# igniter.net
KiCad netlist of a schematic drawn in EAGLE
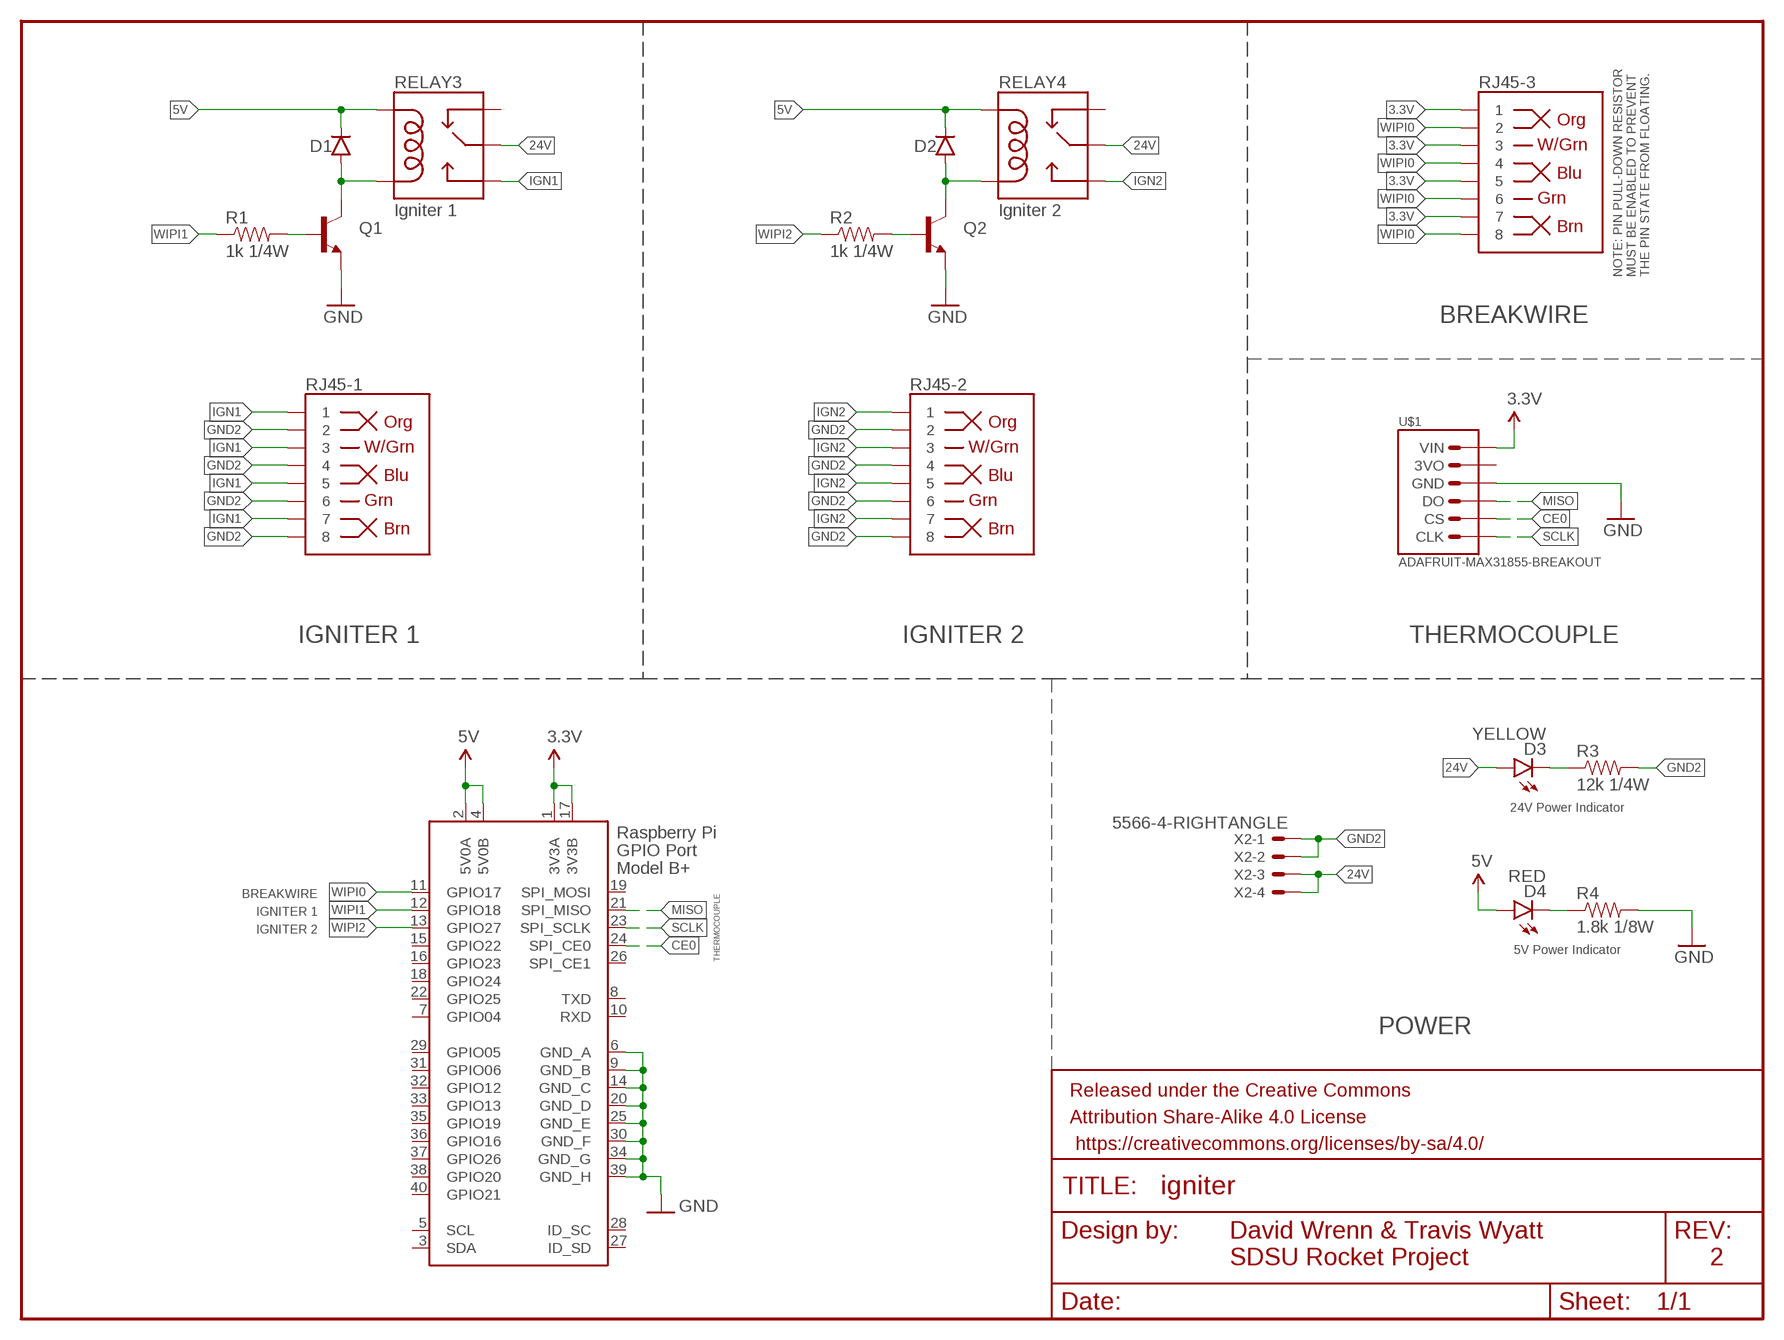
[diagram p0: schematic, sheet 1]

(export (version "E")
  (design (tool "Eeschema 10.0.6"))
  (components
    (comp (ref "D1")
      (value "DIODEPTH")
      (footprint "eagle-import:DIODE-1N4001")
      (libsource (lib "eagle-import") (part "DIODEPTH"))
    )
    (comp (ref "D2")
      (value "DIODEPTH")
      (footprint "eagle-import:DIODE-1N4001")
      (libsource (lib "eagle-import") (part "DIODEPTH"))
    )
    (comp (ref "D3")
      (value "YELLOW")
      (footprint "eagle-import:LED-0603")
      (libsource (lib "eagle-import") (part "LED0603"))
    )
    (comp (ref "D4")
      (value "RED")
      (footprint "eagle-import:LED-0603")
      (libsource (lib "eagle-import") (part "LED0603"))
    )
    (comp (ref "FRAME1")
      (value "FRAME-LETTER")
      (footprint "eagle-import:CREATIVE_COMMONS")
      (fields (field (name "DESIGNER") "NAME"))
      (libsource (lib "eagle-import") (part "FRAME-LETTER"))
    )
    (comp (ref "Q1")
      (value "TRANSISTOR_NPNP2N2222A")
      (footprint "eagle-import:TO-92")
      (libsource (lib "eagle-import") (part "TRANSISTOR_NPNP2N2222A"))
    )
    (comp (ref "Q2")
      (value "TRANSISTOR_NPNP2N2222A")
      (footprint "eagle-import:TO-92")
      (libsource (lib "eagle-import") (part "TRANSISTOR_NPNP2N2222A"))
    )
    (comp (ref "R1")
      (value "1k 1/4W")
      (footprint "eagle-import:AXIAL-0.3")
      (libsource (lib "eagle-import") (part "RESISTORAXIAL-0.3"))
    )
    (comp (ref "R2")
      (value "1k 1/4W")
      (footprint "eagle-import:AXIAL-0.3")
      (libsource (lib "eagle-import") (part "RESISTORAXIAL-0.3"))
    )
    (comp (ref "R3")
      (value "12k 1/4W")
      (footprint "eagle-import:0603-RES")
      (libsource (lib "eagle-import") (part "RESISTOR0603-RES"))
    )
    (comp (ref "R4")
      (value "1.8k 1/8W")
      (footprint "eagle-import:0603-RES")
      (libsource (lib "eagle-import") (part "RESISTOR0603-RES"))
    )
    (comp (ref "RELAY3")
      (value "Igniter 1")
      (footprint "eagle-import:RELAY-G5Q")
      (libsource (lib "eagle-import") (part "RELAYPTH"))
    )
    (comp (ref "RELAY4")
      (value "Igniter 2")
      (footprint "eagle-import:RELAY-G5Q")
      (libsource (lib "eagle-import") (part "RELAYPTH"))
    )
    (comp (ref "RJ45-1")
      (value "RJ45-8PTH")
      (footprint "eagle-import:RJ45-8")
      (libsource (lib "eagle-import") (part "RJ45-8PTH"))
    )
    (comp (ref "RJ45-2")
      (value "RJ45-8PTH")
      (footprint "eagle-import:RJ45-8")
      (libsource (lib "eagle-import") (part "RJ45-8PTH"))
    )
    (comp (ref "RJ45-3")
      (value "RJ45-8PTH")
      (footprint "eagle-import:RJ45-8")
      (libsource (lib "eagle-import") (part "RJ45-8PTH"))
    )
    (comp (ref "U$1")
      (value "ADAFRUIT-MAX31855-BREAKOUT")
      (footprint "eagle-import:ADAFRUIT-MAX31855")
      (libsource (lib "eagle-import") (part "ADAFRUIT-MAX31855-BREAKOUT"))
    )
    (comp (ref "X1")
      (value "RASPI_BOARD_B+#_H")
      (footprint "eagle-import:RASPI_BOARD_B+HAT")
      (libsource (lib "eagle-import") (part "RASPI_BOARD_B+#_H"))
    )
    (comp (ref "X2")
      (value "5566-4-RIGHTANGLE")
      (footprint "eagle-import:5566-4")
      (libsource (lib "eagle-import") (part "5566-4-RIGHTANGLE"))
    )
  )
  (nets
    (net (code "1") (name "3.3V") (class "Default")
      (node (ref "RJ45-3") (pin "1") (pinfunction "1_1") (pintype "bidirectional"))
      (node (ref "RJ45-3") (pin "3") (pinfunction "3_3") (pintype "bidirectional"))
      (node (ref "RJ45-3") (pin "5") (pinfunction "5_5") (pintype "bidirectional"))
      (node (ref "RJ45-3") (pin "7") (pinfunction "7_7") (pintype "bidirectional"))
      (node (ref "U$1") (pin "VIN") (pinfunction "VIN_VIN") (pintype "power_in"))
      (node (ref "X1") (pin "1") (pinfunction "3V3A_1") (pintype "power_in"))
      (node (ref "X1") (pin "17") (pinfunction "3V3B_17") (pintype "power_in"))
    )
    (net (code "2") (name "5V") (class "Default")
      (node (ref "D1") (pin "C") (pinfunction "C_C") (pintype "passive"))
      (node (ref "D2") (pin "C") (pinfunction "C_C") (pintype "passive"))
      (node (ref "D4") (pin "A") (pinfunction "A_A") (pintype "passive"))
      (node (ref "RELAY3") (pin "5") (pinfunction "COIL1_5") (pintype "bidirectional"))
      (node (ref "RELAY4") (pin "5") (pinfunction "COIL1_5") (pintype "bidirectional"))
      (node (ref "X1") (pin "2") (pinfunction "5V0A_2") (pintype "power_in"))
      (node (ref "X1") (pin "4") (pinfunction "5V0B_4") (pintype "power_in"))
    )
    (net (code "3") (name "24V") (class "Default")
      (node (ref "D3") (pin "A") (pinfunction "A_A") (pintype "passive"))
      (node (ref "RELAY3") (pin "2") (pinfunction "MAIN_2") (pintype "bidirectional"))
      (node (ref "RELAY4") (pin "2") (pinfunction "MAIN_2") (pintype "bidirectional"))
      (node (ref "X2") (pin "3") (pinfunction "S_3") (pintype "passive"))
      (node (ref "X2") (pin "4") (pinfunction "S_4") (pintype "passive"))
    )
    (net (code "4") (name "CE0") (class "Default")
      (node (ref "U$1") (pin "CS") (pinfunction "CS_CS") (pintype "input"))
      (node (ref "X1") (pin "24") (pinfunction "SPI_CE0_24") (pintype "bidirectional"))
    )
    (net (code "5") (name "GND") (class "Default")
      (node (ref "Q1") (pin "3") (pinfunction "E_3") (pintype "passive"))
      (node (ref "Q2") (pin "3") (pinfunction "E_3") (pintype "passive"))
      (node (ref "R4") (pin "2") (pinfunction "2_2") (pintype "passive"))
      (node (ref "U$1") (pin "GND") (pinfunction "GND_GND") (pintype "power_in"))
      (node (ref "X1") (pin "14") (pinfunction "GND_C_14") (pintype "power_in"))
      (node (ref "X1") (pin "20") (pinfunction "GND_D_20") (pintype "power_in"))
      (node (ref "X1") (pin "25") (pinfunction "GND_E_25") (pintype "power_in"))
      (node (ref "X1") (pin "30") (pinfunction "GND_F_30") (pintype "power_in"))
      (node (ref "X1") (pin "34") (pinfunction "GND_G_34") (pintype "power_in"))
      (node (ref "X1") (pin "39") (pinfunction "GND_H_39") (pintype "power_in"))
      (node (ref "X1") (pin "6") (pinfunction "GND_A_6") (pintype "power_in"))
      (node (ref "X1") (pin "9") (pinfunction "GND_B_9") (pintype "power_in"))
    )
    (net (code "6") (name "GND2") (class "Default")
      (node (ref "R3") (pin "2") (pinfunction "2_2") (pintype "passive"))
      (node (ref "RJ45-1") (pin "2") (pinfunction "2_2") (pintype "bidirectional"))
      (node (ref "RJ45-1") (pin "4") (pinfunction "4_4") (pintype "bidirectional"))
      (node (ref "RJ45-1") (pin "6") (pinfunction "6_6") (pintype "bidirectional"))
      (node (ref "RJ45-1") (pin "8") (pinfunction "8_8") (pintype "bidirectional"))
      (node (ref "RJ45-2") (pin "2") (pinfunction "2_2") (pintype "bidirectional"))
      (node (ref "RJ45-2") (pin "4") (pinfunction "4_4") (pintype "bidirectional"))
      (node (ref "RJ45-2") (pin "6") (pinfunction "6_6") (pintype "bidirectional"))
      (node (ref "RJ45-2") (pin "8") (pinfunction "8_8") (pintype "bidirectional"))
      (node (ref "X2") (pin "1") (pinfunction "S_1") (pintype "passive"))
      (node (ref "X2") (pin "2") (pinfunction "S_2") (pintype "passive"))
    )
    (net (code "7") (name "IGN1") (class "Default")
      (node (ref "RELAY3") (pin "3") (pinfunction "NO_3") (pintype "bidirectional"))
      (node (ref "RJ45-1") (pin "1") (pinfunction "1_1") (pintype "bidirectional"))
      (node (ref "RJ45-1") (pin "3") (pinfunction "3_3") (pintype "bidirectional"))
      (node (ref "RJ45-1") (pin "5") (pinfunction "5_5") (pintype "bidirectional"))
      (node (ref "RJ45-1") (pin "7") (pinfunction "7_7") (pintype "bidirectional"))
    )
    (net (code "8") (name "IGN2") (class "Default")
      (node (ref "RELAY4") (pin "3") (pinfunction "NO_3") (pintype "bidirectional"))
      (node (ref "RJ45-2") (pin "1") (pinfunction "1_1") (pintype "bidirectional"))
      (node (ref "RJ45-2") (pin "3") (pinfunction "3_3") (pintype "bidirectional"))
      (node (ref "RJ45-2") (pin "5") (pinfunction "5_5") (pintype "bidirectional"))
      (node (ref "RJ45-2") (pin "7") (pinfunction "7_7") (pintype "bidirectional"))
    )
    (net (code "9") (name "MISO") (class "Default")
      (node (ref "U$1") (pin "DO") (pinfunction "DO_DO") (pintype "output"))
      (node (ref "X1") (pin "21") (pinfunction "SPI_MISO_21") (pintype "bidirectional"))
    )
    (net (code "10") (name "Net-(D3-PadC)") (class "Default")
      (node (ref "D3") (pin "C") (pinfunction "C_C") (pintype "passive"))
      (node (ref "R3") (pin "1") (pinfunction "1_1") (pintype "passive"))
    )
    (net (code "11") (name "Net-(D4-PadC)") (class "Default")
      (node (ref "D4") (pin "C") (pinfunction "C_C") (pintype "passive"))
      (node (ref "R4") (pin "1") (pinfunction "1_1") (pintype "passive"))
    )
    (net (code "12") (name "Net-(Q1-B)") (class "Default")
      (node (ref "Q1") (pin "2") (pinfunction "B_2") (pintype "passive"))
      (node (ref "R1") (pin "P$2") (pinfunction "2_P$2") (pintype "passive"))
    )
    (net (code "13") (name "Net-(Q1-C)") (class "Default")
      (node (ref "D1") (pin "A") (pinfunction "A_A") (pintype "passive"))
      (node (ref "Q1") (pin "1") (pinfunction "C_1") (pintype "passive"))
      (node (ref "RELAY3") (pin "1") (pinfunction "COIL2_1") (pintype "bidirectional"))
    )
    (net (code "14") (name "Net-(Q2-B)") (class "Default")
      (node (ref "Q2") (pin "2") (pinfunction "B_2") (pintype "passive"))
      (node (ref "R2") (pin "P$2") (pinfunction "2_P$2") (pintype "passive"))
    )
    (net (code "15") (name "Net-(Q2-C)") (class "Default")
      (node (ref "D2") (pin "A") (pinfunction "A_A") (pintype "passive"))
      (node (ref "Q2") (pin "1") (pinfunction "C_1") (pintype "passive"))
      (node (ref "RELAY4") (pin "1") (pinfunction "COIL2_1") (pintype "bidirectional"))
    )
    (net (code "16") (name "SCLK") (class "Default")
      (node (ref "U$1") (pin "CLK") (pinfunction "CLK_CLK") (pintype "input"))
      (node (ref "X1") (pin "23") (pinfunction "SPI_SCLK_23") (pintype "bidirectional"))
    )
    (net (code "17") (name "WIPI0") (class "Default")
      (node (ref "RJ45-3") (pin "2") (pinfunction "2_2") (pintype "bidirectional"))
      (node (ref "RJ45-3") (pin "4") (pinfunction "4_4") (pintype "bidirectional"))
      (node (ref "RJ45-3") (pin "6") (pinfunction "6_6") (pintype "bidirectional"))
      (node (ref "RJ45-3") (pin "8") (pinfunction "8_8") (pintype "bidirectional"))
      (node (ref "X1") (pin "11") (pinfunction "GPIO17_11") (pintype "bidirectional"))
    )
    (net (code "18") (name "WIPI1") (class "Default")
      (node (ref "R1") (pin "P$1") (pinfunction "1_P$1") (pintype "passive"))
      (node (ref "X1") (pin "12") (pinfunction "GPIO18_12") (pintype "bidirectional"))
    )
    (net (code "19") (name "WIPI2") (class "Default")
      (node (ref "R2") (pin "P$1") (pinfunction "1_P$1") (pintype "passive"))
      (node (ref "X1") (pin "13") (pinfunction "GPIO27_13") (pintype "bidirectional"))
    )
    (net (code "20") (name "unconnected-(RELAY3-NC-Pad4)") (class "Default")
      (node (ref "RELAY3") (pin "4") (pinfunction "NC_4") (pintype "bidirectional"))
    )
    (net (code "21") (name "unconnected-(RELAY4-NC-Pad4)") (class "Default")
      (node (ref "RELAY4") (pin "4") (pinfunction "NC_4") (pintype "bidirectional"))
    )
    (net (code "22") (name "unconnected-(U$1-Pad3VO)") (class "Default")
      (node (ref "U$1") (pin "3VO") (pinfunction "3VO_3VO") (pintype "bidirectional"))
    )
    (net (code "23") (name "unconnected-(X1-GPIO04-Pad7)") (class "Default")
      (node (ref "X1") (pin "7") (pinfunction "GPIO04_7") (pintype "bidirectional"))
    )
    (net (code "24") (name "unconnected-(X1-GPIO05-Pad29)") (class "Default")
      (node (ref "X1") (pin "29") (pinfunction "GPIO05_29") (pintype "no_connect"))
    )
    (net (code "25") (name "unconnected-(X1-GPIO06-Pad31)") (class "Default")
      (node (ref "X1") (pin "31") (pinfunction "GPIO06_31") (pintype "no_connect"))
    )
    (net (code "26") (name "unconnected-(X1-GPIO12-Pad32)") (class "Default")
      (node (ref "X1") (pin "32") (pinfunction "GPIO12_32") (pintype "no_connect"))
    )
    (net (code "27") (name "unconnected-(X1-GPIO13-Pad33)") (class "Default")
      (node (ref "X1") (pin "33") (pinfunction "GPIO13_33") (pintype "no_connect"))
    )
    (net (code "28") (name "unconnected-(X1-GPIO16-Pad36)") (class "Default")
      (node (ref "X1") (pin "36") (pinfunction "GPIO16_36") (pintype "no_connect"))
    )
    (net (code "29") (name "unconnected-(X1-GPIO19-Pad35)") (class "Default")
      (node (ref "X1") (pin "35") (pinfunction "GPIO19_35") (pintype "no_connect"))
    )
    (net (code "30") (name "unconnected-(X1-GPIO20-Pad38)") (class "Default")
      (node (ref "X1") (pin "38") (pinfunction "GPIO20_38") (pintype "no_connect"))
    )
    (net (code "31") (name "unconnected-(X1-GPIO21-Pad40)") (class "Default")
      (node (ref "X1") (pin "40") (pinfunction "GPIO21_40") (pintype "no_connect"))
    )
    (net (code "32") (name "unconnected-(X1-GPIO22-Pad15)") (class "Default")
      (node (ref "X1") (pin "15") (pinfunction "GPIO22_15") (pintype "bidirectional"))
    )
    (net (code "33") (name "unconnected-(X1-GPIO23-Pad16)") (class "Default")
      (node (ref "X1") (pin "16") (pinfunction "GPIO23_16") (pintype "bidirectional"))
    )
    (net (code "34") (name "unconnected-(X1-GPIO24-Pad18)") (class "Default")
      (node (ref "X1") (pin "18") (pinfunction "GPIO24_18") (pintype "bidirectional"))
    )
    (net (code "35") (name "unconnected-(X1-GPIO25-Pad22)") (class "Default")
      (node (ref "X1") (pin "22") (pinfunction "GPIO25_22") (pintype "bidirectional"))
    )
    (net (code "36") (name "unconnected-(X1-GPIO26-Pad37)") (class "Default")
      (node (ref "X1") (pin "37") (pinfunction "GPIO26_37") (pintype "no_connect"))
    )
    (net (code "37") (name "unconnected-(X1-ID_SC-Pad28)") (class "Default")
      (node (ref "X1") (pin "28") (pinfunction "ID_SC_28") (pintype "no_connect"))
    )
    (net (code "38") (name "unconnected-(X1-ID_SD-Pad27)") (class "Default")
      (node (ref "X1") (pin "27") (pinfunction "ID_SD_27") (pintype "no_connect"))
    )
    (net (code "39") (name "unconnected-(X1-RXD-Pad10)") (class "Default")
      (node (ref "X1") (pin "10") (pinfunction "RXD_10") (pintype "bidirectional"))
    )
    (net (code "40") (name "unconnected-(X1-SCL-Pad5)") (class "Default")
      (node (ref "X1") (pin "5") (pinfunction "SCL_5") (pintype "bidirectional"))
    )
    (net (code "41") (name "unconnected-(X1-SDA-Pad3)") (class "Default")
      (node (ref "X1") (pin "3") (pinfunction "SDA_3") (pintype "bidirectional"))
    )
    (net (code "42") (name "unconnected-(X1-SPI_CE1-Pad26)") (class "Default")
      (node (ref "X1") (pin "26") (pinfunction "SPI_CE1_26") (pintype "bidirectional"))
    )
    (net (code "43") (name "unconnected-(X1-SPI_MOSI-Pad19)") (class "Default")
      (node (ref "X1") (pin "19") (pinfunction "SPI_MOSI_19") (pintype "bidirectional"))
    )
    (net (code "44") (name "unconnected-(X1-TXD-Pad8)") (class "Default")
      (node (ref "X1") (pin "8") (pinfunction "TXD_8") (pintype "bidirectional"))
    )
  )
)
